# G021-1.net
KiCad netlist of a schematic drawn in EAGLE
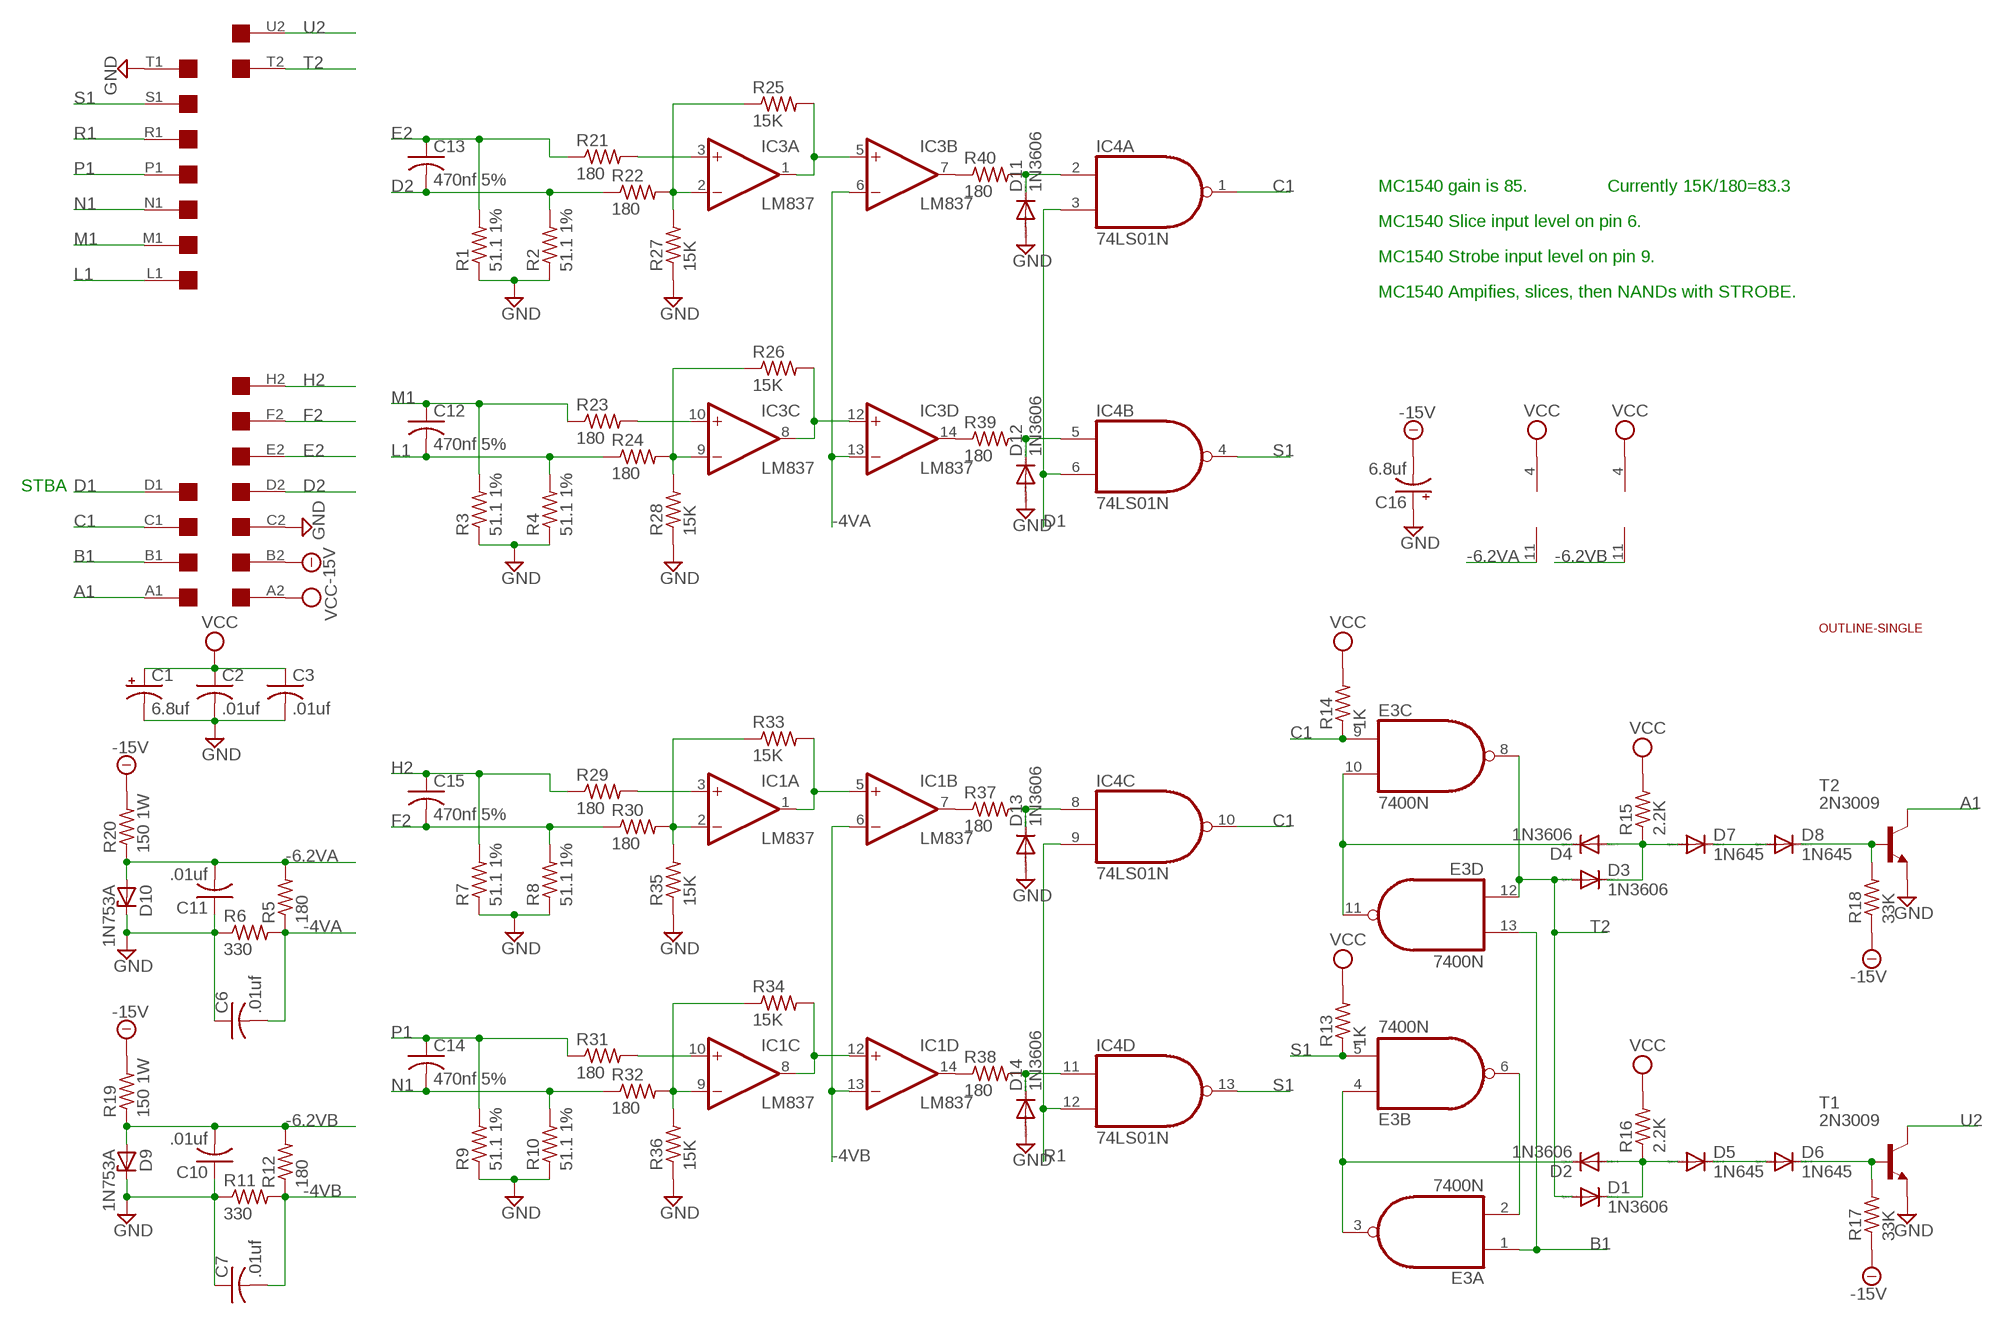
[diagram p0: schematic, sheet 1]

(export (version "E")
  (design (tool "Eeschema 10.0.6"))
  (components
    (comp (ref "C1")
      (value "6.8uf")
      (footprint "eagle-import:E15-5")
      (libsource (lib "eagle-import") (part "CPOL-USE15-5AXIAL"))
    )
    (comp (ref "C2")
      (value ".01uf")
      (footprint "eagle-import:C050-025X075")
      (libsource (lib "eagle-import") (part "C-US050-025X075"))
    )
    (comp (ref "C3")
      (value ".01uf")
      (footprint "eagle-import:C050-025X075")
      (libsource (lib "eagle-import") (part "C-US050-025X075"))
    )
    (comp (ref "C6")
      (value ".01uf")
      (footprint "eagle-import:C050-025X075")
      (libsource (lib "eagle-import") (part "C-US050-025X075"))
    )
    (comp (ref "C7")
      (value ".01uf")
      (footprint "eagle-import:C050-025X075")
      (libsource (lib "eagle-import") (part "C-US050-025X075"))
    )
    (comp (ref "C10")
      (value ".01uf")
      (footprint "eagle-import:C050-025X075")
      (libsource (lib "eagle-import") (part "C-US050-025X075"))
    )
    (comp (ref "C11")
      (value ".01uf")
      (footprint "eagle-import:C050-025X075")
      (libsource (lib "eagle-import") (part "C-US050-025X075"))
    )
    (comp (ref "C12")
      (value "470nf 5%")
      (footprint "eagle-import:C050-025X075")
      (libsource (lib "eagle-import") (part "C-US050-025X075"))
    )
    (comp (ref "C13")
      (value "470nf 5%")
      (footprint "eagle-import:C050-025X075")
      (libsource (lib "eagle-import") (part "C-US050-025X075"))
    )
    (comp (ref "C14")
      (value "470nf 5%")
      (footprint "eagle-import:C050-025X075")
      (libsource (lib "eagle-import") (part "C-US050-025X075"))
    )
    (comp (ref "C15")
      (value "470nf 5%")
      (footprint "eagle-import:C050-025X075")
      (libsource (lib "eagle-import") (part "C-US050-025X075"))
    )
    (comp (ref "C16")
      (value "6.8uf")
      (footprint "eagle-import:E15-5")
      (libsource (lib "eagle-import") (part "CPOL-USE15-5AXIAL"))
    )
    (comp (ref "D1")
      (value "1N3606")
      (footprint "eagle-import:DO35-10")
      (libsource (lib "eagle-import") (part "1N4148DO35-10"))
    )
    (comp (ref "D2")
      (value "1N3606")
      (footprint "eagle-import:DO35-10")
      (libsource (lib "eagle-import") (part "1N4148DO35-10"))
    )
    (comp (ref "D3")
      (value "1N3606")
      (footprint "eagle-import:DO35-10")
      (libsource (lib "eagle-import") (part "1N4148DO35-10"))
    )
    (comp (ref "D4")
      (value "1N3606")
      (footprint "eagle-import:DO35-10")
      (libsource (lib "eagle-import") (part "1N4148DO35-10"))
    )
    (comp (ref "D5")
      (value "1N645")
      (footprint "eagle-import:DO35-10")
      (libsource (lib "eagle-import") (part "1N4148DO35-10"))
    )
    (comp (ref "D6")
      (value "1N645")
      (footprint "eagle-import:DO35-10")
      (libsource (lib "eagle-import") (part "1N4148DO35-10"))
    )
    (comp (ref "D7")
      (value "1N645")
      (footprint "eagle-import:DO35-10")
      (libsource (lib "eagle-import") (part "1N4148DO35-10"))
    )
    (comp (ref "D8")
      (value "1N645")
      (footprint "eagle-import:DO35-10")
      (libsource (lib "eagle-import") (part "1N4148DO35-10"))
    )
    (comp (ref "D9")
      (value "1N753A")
      (footprint "eagle-import:F126Z10")
      (libsource (lib "eagle-import") (part "ZENER-DIODEF126-10"))
    )
    (comp (ref "D10")
      (value "1N753A")
      (footprint "eagle-import:F126Z10")
      (libsource (lib "eagle-import") (part "ZENER-DIODEF126-10"))
    )
    (comp (ref "D11")
      (value "1N3606")
      (footprint "eagle-import:DO35-10")
      (libsource (lib "eagle-import") (part "1N4148DO35-10"))
    )
    (comp (ref "D12")
      (value "1N3606")
      (footprint "eagle-import:DO35-10")
      (libsource (lib "eagle-import") (part "1N4148DO35-10"))
    )
    (comp (ref "D13")
      (value "1N3606")
      (footprint "eagle-import:DO35-10")
      (libsource (lib "eagle-import") (part "1N4148DO35-10"))
    )
    (comp (ref "D14")
      (value "1N3606")
      (footprint "eagle-import:DO35-10")
      (libsource (lib "eagle-import") (part "1N4148DO35-10"))
    )
    (comp (ref "E3")
      (value "7400N")
      (footprint "eagle-import:DIL14")
      (libsource (lib "eagle-import") (part "7400N"))
    )
    (comp (ref "IC1")
      (value "LM837")
      (footprint "eagle-import:DIL14")
      (libsource (lib "eagle-import") (part "OP11P"))
    )
    (comp (ref "IC3")
      (value "LM837")
      (footprint "eagle-import:DIL14")
      (libsource (lib "eagle-import") (part "OP11P"))
    )
    (comp (ref "IC4")
      (value "74LS01N")
      (footprint "eagle-import:DIL14")
      (libsource (lib "eagle-import") (part "7401NLS"))
    )
    (comp (ref "R1")
      (value "51.1 1%")
      (footprint "eagle-import:0207_10")
      (libsource (lib "eagle-import") (part "R-US_0207/10"))
    )
    (comp (ref "R2")
      (value "51.1 1%")
      (footprint "eagle-import:0207_10")
      (libsource (lib "eagle-import") (part "R-US_0207/10"))
    )
    (comp (ref "R3")
      (value "51.1 1%")
      (footprint "eagle-import:0207_10")
      (libsource (lib "eagle-import") (part "R-US_0207/10"))
    )
    (comp (ref "R4")
      (value "51.1 1%")
      (footprint "eagle-import:0207_10")
      (libsource (lib "eagle-import") (part "R-US_0207/10"))
    )
    (comp (ref "R5")
      (value "180")
      (footprint "eagle-import:0207_10")
      (libsource (lib "eagle-import") (part "R-US_0207/10"))
    )
    (comp (ref "R6")
      (value "330")
      (footprint "eagle-import:0207_10")
      (libsource (lib "eagle-import") (part "R-US_0207/10"))
    )
    (comp (ref "R7")
      (value "51.1 1%")
      (footprint "eagle-import:0207_10")
      (libsource (lib "eagle-import") (part "R-US_0207/10"))
    )
    (comp (ref "R8")
      (value "51.1 1%")
      (footprint "eagle-import:0207_10")
      (libsource (lib "eagle-import") (part "R-US_0207/10"))
    )
    (comp (ref "R9")
      (value "51.1 1%")
      (footprint "eagle-import:0207_10")
      (libsource (lib "eagle-import") (part "R-US_0207/10"))
    )
    (comp (ref "R10")
      (value "51.1 1%")
      (footprint "eagle-import:0207_10")
      (libsource (lib "eagle-import") (part "R-US_0207/10"))
    )
    (comp (ref "R11")
      (value "330")
      (footprint "eagle-import:0207_10")
      (libsource (lib "eagle-import") (part "R-US_0207/10"))
    )
    (comp (ref "R12")
      (value "180")
      (footprint "eagle-import:0207_10")
      (libsource (lib "eagle-import") (part "R-US_0207/10"))
    )
    (comp (ref "R13")
      (value "1K")
      (footprint "eagle-import:0207_10")
      (libsource (lib "eagle-import") (part "R-US_0207/10"))
    )
    (comp (ref "R14")
      (value "1K")
      (footprint "eagle-import:0207_10")
      (libsource (lib "eagle-import") (part "R-US_0207/10"))
    )
    (comp (ref "R15")
      (value "2.2K")
      (footprint "eagle-import:0207_10")
      (libsource (lib "eagle-import") (part "R-US_0207/10"))
    )
    (comp (ref "R16")
      (value "2.2K")
      (footprint "eagle-import:0207_10")
      (libsource (lib "eagle-import") (part "R-US_0207/10"))
    )
    (comp (ref "R17")
      (value "33K")
      (footprint "eagle-import:0207_10")
      (libsource (lib "eagle-import") (part "R-US_0207/10"))
    )
    (comp (ref "R18")
      (value "33K")
      (footprint "eagle-import:0207_10")
      (libsource (lib "eagle-import") (part "R-US_0207/10"))
    )
    (comp (ref "R19")
      (value "150 1W")
      (footprint "eagle-import:0414_15")
      (libsource (lib "eagle-import") (part "R-US_0414/15"))
    )
    (comp (ref "R20")
      (value "150 1W")
      (footprint "eagle-import:0414_15")
      (libsource (lib "eagle-import") (part "R-US_0414/15"))
    )
    (comp (ref "R21")
      (value "180")
      (footprint "eagle-import:0207_10")
      (libsource (lib "eagle-import") (part "R-US_0207/10"))
    )
    (comp (ref "R22")
      (value "180")
      (footprint "eagle-import:0207_10")
      (libsource (lib "eagle-import") (part "R-US_0207/10"))
    )
    (comp (ref "R23")
      (value "180")
      (footprint "eagle-import:0207_10")
      (libsource (lib "eagle-import") (part "R-US_0207/10"))
    )
    (comp (ref "R24")
      (value "180")
      (footprint "eagle-import:0207_10")
      (libsource (lib "eagle-import") (part "R-US_0207/10"))
    )
    (comp (ref "R25")
      (value "15K")
      (footprint "eagle-import:0207_10")
      (libsource (lib "eagle-import") (part "R-US_0207/10"))
    )
    (comp (ref "R26")
      (value "15K")
      (footprint "eagle-import:0207_10")
      (libsource (lib "eagle-import") (part "R-US_0207/10"))
    )
    (comp (ref "R27")
      (value "15K")
      (footprint "eagle-import:0207_10")
      (libsource (lib "eagle-import") (part "R-US_0207/10"))
    )
    (comp (ref "R28")
      (value "15K")
      (footprint "eagle-import:0207_10")
      (libsource (lib "eagle-import") (part "R-US_0207/10"))
    )
    (comp (ref "R29")
      (value "180")
      (footprint "eagle-import:0207_10")
      (libsource (lib "eagle-import") (part "R-US_0207/10"))
    )
    (comp (ref "R30")
      (value "180")
      (footprint "eagle-import:0207_10")
      (libsource (lib "eagle-import") (part "R-US_0207/10"))
    )
    (comp (ref "R31")
      (value "180")
      (footprint "eagle-import:0207_10")
      (libsource (lib "eagle-import") (part "R-US_0207/10"))
    )
    (comp (ref "R32")
      (value "180")
      (footprint "eagle-import:0207_10")
      (libsource (lib "eagle-import") (part "R-US_0207/10"))
    )
    (comp (ref "R33")
      (value "15K")
      (footprint "eagle-import:0207_10")
      (libsource (lib "eagle-import") (part "R-US_0207/10"))
    )
    (comp (ref "R34")
      (value "15K")
      (footprint "eagle-import:0207_10")
      (libsource (lib "eagle-import") (part "R-US_0207/10"))
    )
    (comp (ref "R35")
      (value "15K")
      (footprint "eagle-import:0207_10")
      (libsource (lib "eagle-import") (part "R-US_0207/10"))
    )
    (comp (ref "R36")
      (value "15K")
      (footprint "eagle-import:0207_10")
      (libsource (lib "eagle-import") (part "R-US_0207/10"))
    )
    (comp (ref "R37")
      (value "180")
      (footprint "eagle-import:0207_10")
      (libsource (lib "eagle-import") (part "R-US_0207/10"))
    )
    (comp (ref "R38")
      (value "180")
      (footprint "eagle-import:0207_10")
      (libsource (lib "eagle-import") (part "R-US_0207/10"))
    )
    (comp (ref "R39")
      (value "180")
      (footprint "eagle-import:0207_10")
      (libsource (lib "eagle-import") (part "R-US_0207/10"))
    )
    (comp (ref "R40")
      (value "180")
      (footprint "eagle-import:0207_10")
      (libsource (lib "eagle-import") (part "R-US_0207/10"))
    )
    (comp (ref "T1")
      (value "2N3009")
      (footprint "eagle-import:TO92")
      (libsource (lib "eagle-import") (part "2N3565"))
    )
    (comp (ref "T2")
      (value "2N3009")
      (footprint "eagle-import:TO92")
      (libsource (lib "eagle-import") (part "2N3565"))
    )
    (comp (ref "U$1")
      (value "SINGLE")
      (footprint "eagle-import:EDGE-CON2")
      (libsource (lib "eagle-import") (part "SINGLE"))
    )
    (comp (ref "U$2")
      (value "OUTLINE-SINGLE")
      (footprint "eagle-import:SINGLE")
      (libsource (lib "eagle-import") (part "OUTLINE-SINGLE"))
    )
  )
  (nets
    (net (code "1") (name "-15V") (class "Default")
      (node (ref "C16") (pin "-") (pinfunction "-_-") (pintype "passive"))
      (node (ref "R17") (pin "1") (pinfunction "1_1") (pintype "passive"))
      (node (ref "R18") (pin "1") (pinfunction "1_1") (pintype "passive"))
      (node (ref "R19") (pin "2") (pinfunction "2_2") (pintype "passive"))
      (node (ref "R20") (pin "2") (pinfunction "2_2") (pintype "passive"))
      (node (ref "U$1") (pin "B2") (pinfunction "1_B2") (pintype "bidirectional"))
    )
    (net (code "2") (name "/-4VA") (class "Default")
      (node (ref "C6") (pin "2") (pinfunction "2_2") (pintype "passive"))
      (node (ref "IC3") (pin "13") (pinfunction "-IN_13") (pintype "input"))
      (node (ref "IC3") (pin "6") (pinfunction "-IN_6") (pintype "input"))
      (node (ref "R5") (pin "1") (pinfunction "1_1") (pintype "passive"))
      (node (ref "R6") (pin "2") (pinfunction "2_2") (pintype "passive"))
    )
    (net (code "3") (name "/-4VB") (class "Default")
      (node (ref "C7") (pin "2") (pinfunction "2_2") (pintype "passive"))
      (node (ref "IC1") (pin "13") (pinfunction "-IN_13") (pintype "input"))
      (node (ref "IC1") (pin "6") (pinfunction "-IN_6") (pintype "input"))
      (node (ref "R11") (pin "2") (pinfunction "2_2") (pintype "passive"))
      (node (ref "R12") (pin "1") (pinfunction "1_1") (pintype "passive"))
    )
    (net (code "4") (name "/-6.2VA") (class "Default")
      (node (ref "C11") (pin "2") (pinfunction "2_2") (pintype "passive"))
      (node (ref "D10") (pin "A") (pinfunction "A_A") (pintype "passive"))
      (node (ref "IC3") (pin "11") (pinfunction "V-_11") (pintype "power_in"))
      (node (ref "R20") (pin "1") (pinfunction "1_1") (pintype "passive"))
      (node (ref "R5") (pin "2") (pinfunction "2_2") (pintype "passive"))
    )
    (net (code "5") (name "/-6.2VB") (class "Default")
      (node (ref "C10") (pin "2") (pinfunction "2_2") (pintype "passive"))
      (node (ref "D9") (pin "A") (pinfunction "A_A") (pintype "passive"))
      (node (ref "IC1") (pin "11") (pinfunction "V-_11") (pintype "power_in"))
      (node (ref "R12") (pin "2") (pinfunction "2_2") (pintype "passive"))
      (node (ref "R19") (pin "1") (pinfunction "1_1") (pintype "passive"))
    )
    (net (code "6") (name "/A1") (class "Default")
      (node (ref "T2") (pin "1") (pinfunction "C_1") (pintype "passive"))
      (node (ref "U$1") (pin "A1") (pinfunction "1_A1") (pintype "bidirectional"))
    )
    (net (code "7") (name "/B1") (class "Default")
      (node (ref "E3") (pin "1") (pinfunction "I0_1") (pintype "input"))
      (node (ref "E3") (pin "13") (pinfunction "I1_13") (pintype "input"))
      (node (ref "U$1") (pin "B1") (pinfunction "1_B1") (pintype "bidirectional"))
    )
    (net (code "8") (name "/C1") (class "Default")
      (node (ref "E3") (pin "9") (pinfunction "I0_9") (pintype "input"))
      (node (ref "IC4") (pin "1") (pinfunction "O_1") (pintype "open_collector"))
      (node (ref "IC4") (pin "10") (pinfunction "O_10") (pintype "open_collector"))
      (node (ref "R14") (pin "1") (pinfunction "1_1") (pintype "passive"))
      (node (ref "U$1") (pin "C1") (pinfunction "1_C1") (pintype "bidirectional"))
    )
    (net (code "9") (name "/D1") (class "Default")
      (node (ref "IC4") (pin "3") (pinfunction "I1_3") (pintype "input"))
      (node (ref "IC4") (pin "6") (pinfunction "I1_6") (pintype "input"))
      (node (ref "U$1") (pin "D1") (pinfunction "1_D1") (pintype "bidirectional"))
    )
    (net (code "10") (name "/D2") (class "Default")
      (node (ref "C13") (pin "2") (pinfunction "2_2") (pintype "passive"))
      (node (ref "R2") (pin "2") (pinfunction "2_2") (pintype "passive"))
      (node (ref "R22") (pin "1") (pinfunction "1_1") (pintype "passive"))
      (node (ref "U$1") (pin "D2") (pinfunction "1_D2") (pintype "bidirectional"))
    )
    (net (code "11") (name "/E2") (class "Default")
      (node (ref "C13") (pin "1") (pinfunction "1_1") (pintype "passive"))
      (node (ref "R1") (pin "2") (pinfunction "2_2") (pintype "passive"))
      (node (ref "R21") (pin "1") (pinfunction "1_1") (pintype "passive"))
      (node (ref "U$1") (pin "E2") (pinfunction "1_E2") (pintype "bidirectional"))
    )
    (net (code "12") (name "/F2") (class "Default")
      (node (ref "C15") (pin "2") (pinfunction "2_2") (pintype "passive"))
      (node (ref "R30") (pin "1") (pinfunction "1_1") (pintype "passive"))
      (node (ref "R8") (pin "2") (pinfunction "2_2") (pintype "passive"))
      (node (ref "U$1") (pin "F2") (pinfunction "1_F2") (pintype "bidirectional"))
    )
    (net (code "13") (name "/H2") (class "Default")
      (node (ref "C15") (pin "1") (pinfunction "1_1") (pintype "passive"))
      (node (ref "R29") (pin "1") (pinfunction "1_1") (pintype "passive"))
      (node (ref "R7") (pin "2") (pinfunction "2_2") (pintype "passive"))
      (node (ref "U$1") (pin "H2") (pinfunction "1_H2") (pintype "bidirectional"))
    )
    (net (code "14") (name "/L1") (class "Default")
      (node (ref "C12") (pin "2") (pinfunction "2_2") (pintype "passive"))
      (node (ref "R24") (pin "1") (pinfunction "1_1") (pintype "passive"))
      (node (ref "R4") (pin "2") (pinfunction "2_2") (pintype "passive"))
      (node (ref "U$1") (pin "L1") (pinfunction "1_L1") (pintype "bidirectional"))
    )
    (net (code "15") (name "/M1") (class "Default")
      (node (ref "C12") (pin "1") (pinfunction "1_1") (pintype "passive"))
      (node (ref "R23") (pin "1") (pinfunction "1_1") (pintype "passive"))
      (node (ref "R3") (pin "2") (pinfunction "2_2") (pintype "passive"))
      (node (ref "U$1") (pin "M1") (pinfunction "1_M1") (pintype "bidirectional"))
    )
    (net (code "16") (name "/N1") (class "Default")
      (node (ref "C14") (pin "2") (pinfunction "2_2") (pintype "passive"))
      (node (ref "R10") (pin "2") (pinfunction "2_2") (pintype "passive"))
      (node (ref "R32") (pin "1") (pinfunction "1_1") (pintype "passive"))
      (node (ref "U$1") (pin "N1") (pinfunction "1_N1") (pintype "bidirectional"))
    )
    (net (code "17") (name "/P1") (class "Default")
      (node (ref "C14") (pin "1") (pinfunction "1_1") (pintype "passive"))
      (node (ref "R31") (pin "1") (pinfunction "1_1") (pintype "passive"))
      (node (ref "R9") (pin "2") (pinfunction "2_2") (pintype "passive"))
      (node (ref "U$1") (pin "P1") (pinfunction "1_P1") (pintype "bidirectional"))
    )
    (net (code "18") (name "/R1") (class "Default")
      (node (ref "IC4") (pin "12") (pinfunction "I1_12") (pintype "input"))
      (node (ref "IC4") (pin "9") (pinfunction "I1_9") (pintype "input"))
      (node (ref "U$1") (pin "R1") (pinfunction "1_R1") (pintype "bidirectional"))
    )
    (net (code "19") (name "/S1") (class "Default")
      (node (ref "E3") (pin "5") (pinfunction "I1_5") (pintype "input"))
      (node (ref "IC4") (pin "13") (pinfunction "O_13") (pintype "open_collector"))
      (node (ref "IC4") (pin "4") (pinfunction "O_4") (pintype "open_collector"))
      (node (ref "R13") (pin "1") (pinfunction "1_1") (pintype "passive"))
      (node (ref "U$1") (pin "S1") (pinfunction "1_S1") (pintype "bidirectional"))
    )
    (net (code "20") (name "/T2") (class "Default")
      (node (ref "D1") (pin "A") (pinfunction "A_A") (pintype "passive"))
      (node (ref "D3") (pin "A") (pinfunction "A_A") (pintype "passive"))
      (node (ref "E3") (pin "12") (pinfunction "I0_12") (pintype "input"))
      (node (ref "E3") (pin "8") (pinfunction "O_8") (pintype "output"))
      (node (ref "U$1") (pin "T2") (pinfunction "1_T2") (pintype "bidirectional"))
    )
    (net (code "21") (name "/U2") (class "Default")
      (node (ref "T1") (pin "1") (pinfunction "C_1") (pintype "passive"))
      (node (ref "U$1") (pin "U2") (pinfunction "1_U2") (pintype "bidirectional"))
    )
    (net (code "22") (name "GND") (class "Default")
      (node (ref "C1") (pin "-") (pinfunction "-_-") (pintype "passive"))
      (node (ref "C10") (pin "1") (pinfunction "1_1") (pintype "passive"))
      (node (ref "C11") (pin "1") (pinfunction "1_1") (pintype "passive"))
      (node (ref "C16") (pin "+") (pinfunction "+_+") (pintype "passive"))
      (node (ref "C2") (pin "2") (pinfunction "2_2") (pintype "passive"))
      (node (ref "C3") (pin "2") (pinfunction "2_2") (pintype "passive"))
      (node (ref "C6") (pin "1") (pinfunction "1_1") (pintype "passive"))
      (node (ref "C7") (pin "1") (pinfunction "1_1") (pintype "passive"))
      (node (ref "D10") (pin "C") (pinfunction "C_C") (pintype "passive"))
      (node (ref "D11") (pin "A") (pinfunction "A_A") (pintype "passive"))
      (node (ref "D12") (pin "A") (pinfunction "A_A") (pintype "passive"))
      (node (ref "D13") (pin "A") (pinfunction "A_A") (pintype "passive"))
      (node (ref "D14") (pin "A") (pinfunction "A_A") (pintype "passive"))
      (node (ref "D9") (pin "C") (pinfunction "C_C") (pintype "passive"))
      (node (ref "R1") (pin "1") (pinfunction "1_1") (pintype "passive"))
      (node (ref "R10") (pin "1") (pinfunction "1_1") (pintype "passive"))
      (node (ref "R11") (pin "1") (pinfunction "1_1") (pintype "passive"))
      (node (ref "R2") (pin "1") (pinfunction "1_1") (pintype "passive"))
      (node (ref "R27") (pin "1") (pinfunction "1_1") (pintype "passive"))
      (node (ref "R28") (pin "1") (pinfunction "1_1") (pintype "passive"))
      (node (ref "R3") (pin "1") (pinfunction "1_1") (pintype "passive"))
      (node (ref "R35") (pin "1") (pinfunction "1_1") (pintype "passive"))
      (node (ref "R36") (pin "1") (pinfunction "1_1") (pintype "passive"))
      (node (ref "R4") (pin "1") (pinfunction "1_1") (pintype "passive"))
      (node (ref "R6") (pin "1") (pinfunction "1_1") (pintype "passive"))
      (node (ref "R7") (pin "1") (pinfunction "1_1") (pintype "passive"))
      (node (ref "R8") (pin "1") (pinfunction "1_1") (pintype "passive"))
      (node (ref "R9") (pin "1") (pinfunction "1_1") (pintype "passive"))
      (node (ref "T1") (pin "3") (pinfunction "E_3") (pintype "passive"))
      (node (ref "T2") (pin "3") (pinfunction "E_3") (pintype "passive"))
      (node (ref "U$1") (pin "C2") (pinfunction "1_C2") (pintype "bidirectional"))
      (node (ref "U$1") (pin "T1") (pinfunction "1_T1") (pintype "bidirectional"))
    )
    (net (code "23") (name "Net-(D1-PadC)") (class "Default")
      (node (ref "D1") (pin "C") (pinfunction "C_C") (pintype "passive"))
      (node (ref "D2") (pin "A") (pinfunction "A_A") (pintype "passive"))
      (node (ref "D5") (pin "A") (pinfunction "A_A") (pintype "passive"))
      (node (ref "R16") (pin "1") (pinfunction "1_1") (pintype "passive"))
    )
    (net (code "24") (name "Net-(D3-PadC)") (class "Default")
      (node (ref "D3") (pin "C") (pinfunction "C_C") (pintype "passive"))
      (node (ref "D4") (pin "A") (pinfunction "A_A") (pintype "passive"))
      (node (ref "D7") (pin "A") (pinfunction "A_A") (pintype "passive"))
      (node (ref "R15") (pin "1") (pinfunction "1_1") (pintype "passive"))
    )
    (net (code "25") (name "Net-(D5-PadC)") (class "Default")
      (node (ref "D5") (pin "C") (pinfunction "C_C") (pintype "passive"))
      (node (ref "D6") (pin "A") (pinfunction "A_A") (pintype "passive"))
    )
    (net (code "26") (name "Net-(D7-PadC)") (class "Default")
      (node (ref "D7") (pin "C") (pinfunction "C_C") (pintype "passive"))
      (node (ref "D8") (pin "A") (pinfunction "A_A") (pintype "passive"))
    )
    (net (code "27") (name "Net-(E3A-I1)") (class "Default")
      (node (ref "E3") (pin "2") (pinfunction "I1_2") (pintype "input"))
      (node (ref "E3") (pin "6") (pinfunction "O_6") (pintype "output"))
    )
    (net (code "28") (name "Net-(E3A-O)") (class "Default")
      (node (ref "D2") (pin "C") (pinfunction "C_C") (pintype "passive"))
      (node (ref "E3") (pin "3") (pinfunction "O_3") (pintype "output"))
      (node (ref "E3") (pin "4") (pinfunction "I0_4") (pintype "input"))
    )
    (net (code "29") (name "Net-(E3C-I1)") (class "Default")
      (node (ref "D4") (pin "C") (pinfunction "C_C") (pintype "passive"))
      (node (ref "E3") (pin "10") (pinfunction "I1_10") (pintype "input"))
      (node (ref "E3") (pin "11") (pinfunction "O_11") (pintype "output"))
    )
    (net (code "30") (name "Net-(IC1A-+IN)") (class "Default")
      (node (ref "IC1") (pin "3") (pinfunction "+IN_3") (pintype "input"))
      (node (ref "R29") (pin "2") (pinfunction "2_2") (pintype "passive"))
    )
    (net (code "31") (name "Net-(IC1A--IN)") (class "Default")
      (node (ref "IC1") (pin "2") (pinfunction "-IN_2") (pintype "input"))
      (node (ref "R30") (pin "2") (pinfunction "2_2") (pintype "passive"))
      (node (ref "R33") (pin "1") (pinfunction "1_1") (pintype "passive"))
      (node (ref "R35") (pin "2") (pinfunction "2_2") (pintype "passive"))
    )
    (net (code "32") (name "Net-(IC1A-OUT)") (class "Default")
      (node (ref "IC1") (pin "1") (pinfunction "OUT_1") (pintype "output"))
      (node (ref "IC1") (pin "5") (pinfunction "+IN_5") (pintype "input"))
      (node (ref "R33") (pin "2") (pinfunction "2_2") (pintype "passive"))
    )
    (net (code "33") (name "Net-(IC1B-OUT)") (class "Default")
      (node (ref "IC1") (pin "7") (pinfunction "OUT_7") (pintype "output"))
      (node (ref "R37") (pin "1") (pinfunction "1_1") (pintype "passive"))
    )
    (net (code "34") (name "Net-(IC1C-+IN)") (class "Default")
      (node (ref "IC1") (pin "10") (pinfunction "+IN_10") (pintype "input"))
      (node (ref "R31") (pin "2") (pinfunction "2_2") (pintype "passive"))
    )
    (net (code "35") (name "Net-(IC1C--IN)") (class "Default")
      (node (ref "IC1") (pin "9") (pinfunction "-IN_9") (pintype "input"))
      (node (ref "R32") (pin "2") (pinfunction "2_2") (pintype "passive"))
      (node (ref "R34") (pin "1") (pinfunction "1_1") (pintype "passive"))
      (node (ref "R36") (pin "2") (pinfunction "2_2") (pintype "passive"))
    )
    (net (code "36") (name "Net-(IC1C-OUT)") (class "Default")
      (node (ref "IC1") (pin "12") (pinfunction "+IN_12") (pintype "input"))
      (node (ref "IC1") (pin "8") (pinfunction "OUT_8") (pintype "output"))
      (node (ref "R34") (pin "2") (pinfunction "2_2") (pintype "passive"))
    )
    (net (code "37") (name "Net-(IC1D-OUT)") (class "Default")
      (node (ref "IC1") (pin "14") (pinfunction "OUT_14") (pintype "output"))
      (node (ref "R38") (pin "1") (pinfunction "1_1") (pintype "passive"))
    )
    (net (code "38") (name "Net-(IC3A-+IN)") (class "Default")
      (node (ref "IC3") (pin "3") (pinfunction "+IN_3") (pintype "input"))
      (node (ref "R21") (pin "2") (pinfunction "2_2") (pintype "passive"))
    )
    (net (code "39") (name "Net-(IC3A--IN)") (class "Default")
      (node (ref "IC3") (pin "2") (pinfunction "-IN_2") (pintype "input"))
      (node (ref "R22") (pin "2") (pinfunction "2_2") (pintype "passive"))
      (node (ref "R25") (pin "1") (pinfunction "1_1") (pintype "passive"))
      (node (ref "R27") (pin "2") (pinfunction "2_2") (pintype "passive"))
    )
    (net (code "40") (name "Net-(IC3A-OUT)") (class "Default")
      (node (ref "IC3") (pin "1") (pinfunction "OUT_1") (pintype "output"))
      (node (ref "IC3") (pin "5") (pinfunction "+IN_5") (pintype "input"))
      (node (ref "R25") (pin "2") (pinfunction "2_2") (pintype "passive"))
    )
    (net (code "41") (name "Net-(IC3B-OUT)") (class "Default")
      (node (ref "IC3") (pin "7") (pinfunction "OUT_7") (pintype "output"))
      (node (ref "R40") (pin "1") (pinfunction "1_1") (pintype "passive"))
    )
    (net (code "42") (name "Net-(IC3C-+IN)") (class "Default")
      (node (ref "IC3") (pin "10") (pinfunction "+IN_10") (pintype "input"))
      (node (ref "R23") (pin "2") (pinfunction "2_2") (pintype "passive"))
    )
    (net (code "43") (name "Net-(IC3C--IN)") (class "Default")
      (node (ref "IC3") (pin "9") (pinfunction "-IN_9") (pintype "input"))
      (node (ref "R24") (pin "2") (pinfunction "2_2") (pintype "passive"))
      (node (ref "R26") (pin "1") (pinfunction "1_1") (pintype "passive"))
      (node (ref "R28") (pin "2") (pinfunction "2_2") (pintype "passive"))
    )
    (net (code "44") (name "Net-(IC3C-OUT)") (class "Default")
      (node (ref "IC3") (pin "12") (pinfunction "+IN_12") (pintype "input"))
      (node (ref "IC3") (pin "8") (pinfunction "OUT_8") (pintype "output"))
      (node (ref "R26") (pin "2") (pinfunction "2_2") (pintype "passive"))
    )
    (net (code "45") (name "Net-(IC3D-OUT)") (class "Default")
      (node (ref "IC3") (pin "14") (pinfunction "OUT_14") (pintype "output"))
      (node (ref "R39") (pin "1") (pinfunction "1_1") (pintype "passive"))
    )
    (net (code "46") (name "Net-(IC4A-I0)") (class "Default")
      (node (ref "D11") (pin "C") (pinfunction "C_C") (pintype "passive"))
      (node (ref "IC4") (pin "2") (pinfunction "I0_2") (pintype "input"))
      (node (ref "R40") (pin "2") (pinfunction "2_2") (pintype "passive"))
    )
    (net (code "47") (name "Net-(IC4B-I0)") (class "Default")
      (node (ref "D12") (pin "C") (pinfunction "C_C") (pintype "passive"))
      (node (ref "IC4") (pin "5") (pinfunction "I0_5") (pintype "input"))
      (node (ref "R39") (pin "2") (pinfunction "2_2") (pintype "passive"))
    )
    (net (code "48") (name "Net-(IC4C-I0)") (class "Default")
      (node (ref "D13") (pin "C") (pinfunction "C_C") (pintype "passive"))
      (node (ref "IC4") (pin "8") (pinfunction "I0_8") (pintype "input"))
      (node (ref "R37") (pin "2") (pinfunction "2_2") (pintype "passive"))
    )
    (net (code "49") (name "Net-(IC4D-I0)") (class "Default")
      (node (ref "D14") (pin "C") (pinfunction "C_C") (pintype "passive"))
      (node (ref "IC4") (pin "11") (pinfunction "I0_11") (pintype "input"))
      (node (ref "R38") (pin "2") (pinfunction "2_2") (pintype "passive"))
    )
    (net (code "50") (name "Net-(T1-B)") (class "Default")
      (node (ref "D6") (pin "C") (pinfunction "C_C") (pintype "passive"))
      (node (ref "R17") (pin "2") (pinfunction "2_2") (pintype "passive"))
      (node (ref "T1") (pin "2") (pinfunction "B_2") (pintype "passive"))
    )
    (net (code "51") (name "Net-(T2-B)") (class "Default")
      (node (ref "D8") (pin "C") (pinfunction "C_C") (pintype "passive"))
      (node (ref "R18") (pin "2") (pinfunction "2_2") (pintype "passive"))
      (node (ref "T2") (pin "2") (pinfunction "B_2") (pintype "passive"))
    )
    (net (code "52") (name "VCC") (class "Default")
      (node (ref "C1") (pin "+") (pinfunction "+_+") (pintype "passive"))
      (node (ref "C2") (pin "1") (pinfunction "1_1") (pintype "passive"))
      (node (ref "C3") (pin "1") (pinfunction "1_1") (pintype "passive"))
      (node (ref "IC1") (pin "4") (pinfunction "V+_4") (pintype "power_in"))
      (node (ref "IC3") (pin "4") (pinfunction "V+_4") (pintype "power_in"))
      (node (ref "R13") (pin "2") (pinfunction "2_2") (pintype "passive"))
      (node (ref "R14") (pin "2") (pinfunction "2_2") (pintype "passive"))
      (node (ref "R15") (pin "2") (pinfunction "2_2") (pintype "passive"))
      (node (ref "R16") (pin "2") (pinfunction "2_2") (pintype "passive"))
      (node (ref "U$1") (pin "A2") (pinfunction "1_A2") (pintype "bidirectional"))
    )
  )
)
